# 19_SMB1358.net
KiCad netlist of a schematic drawn in Altium Designer
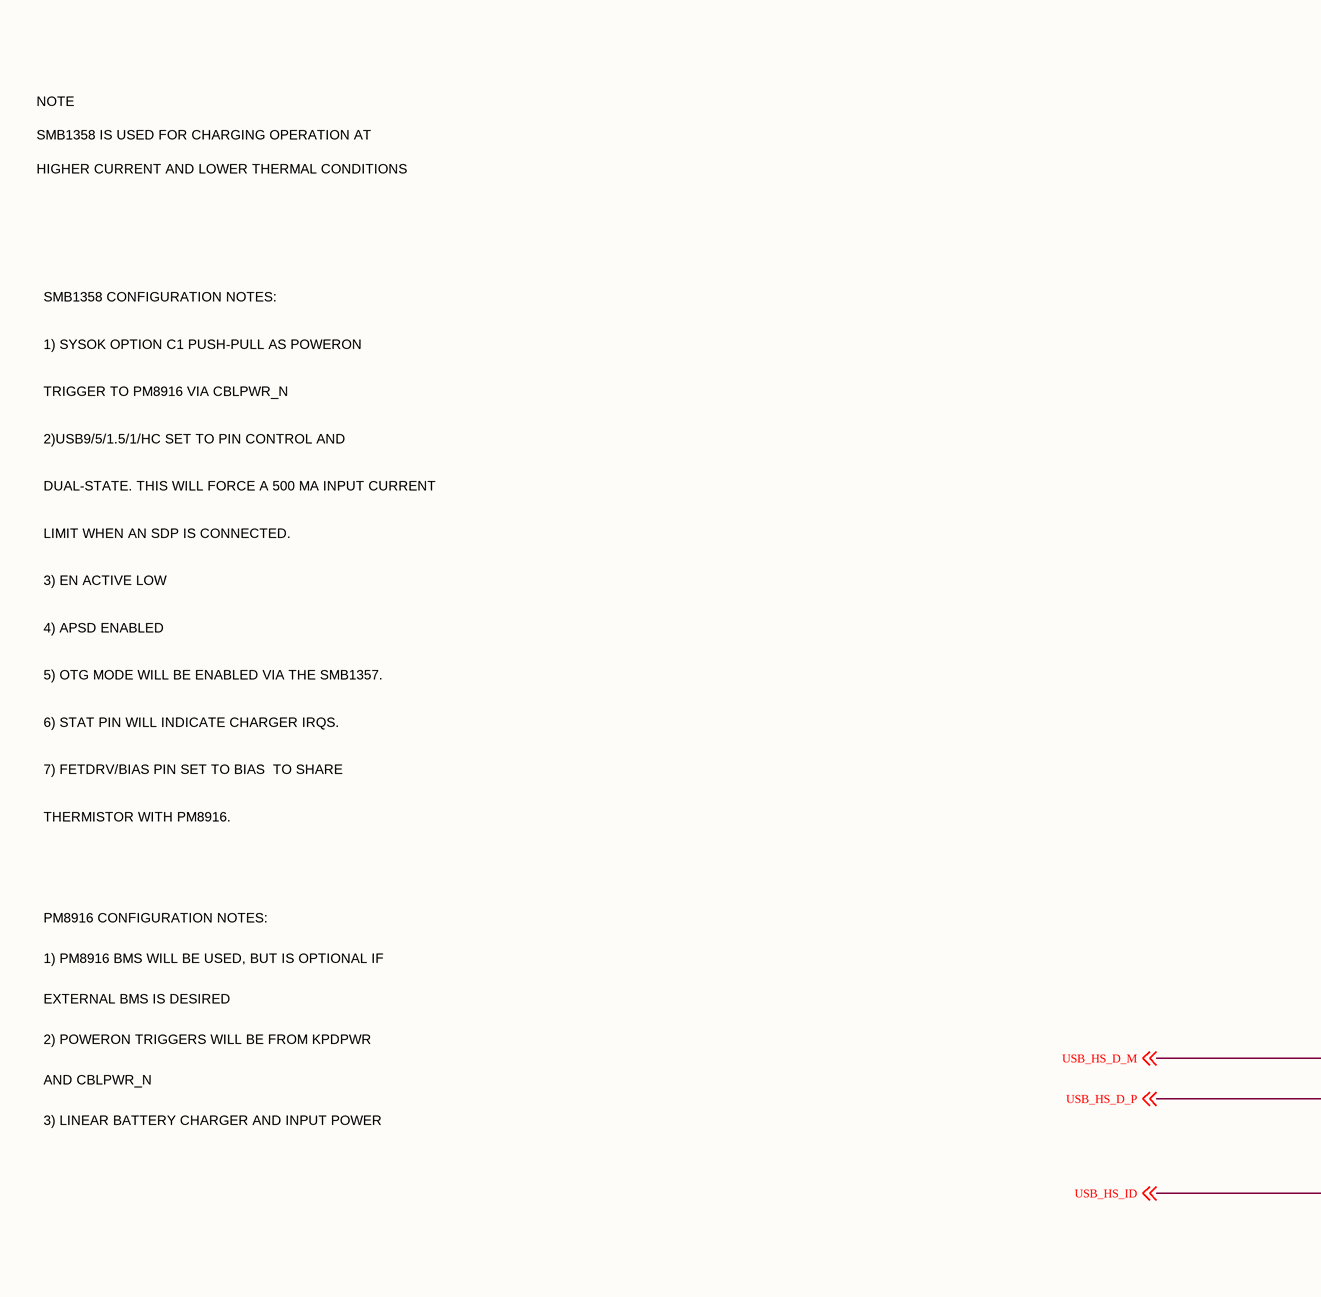
[diagram p0: 19 SMB1358.SchDoc, top left]
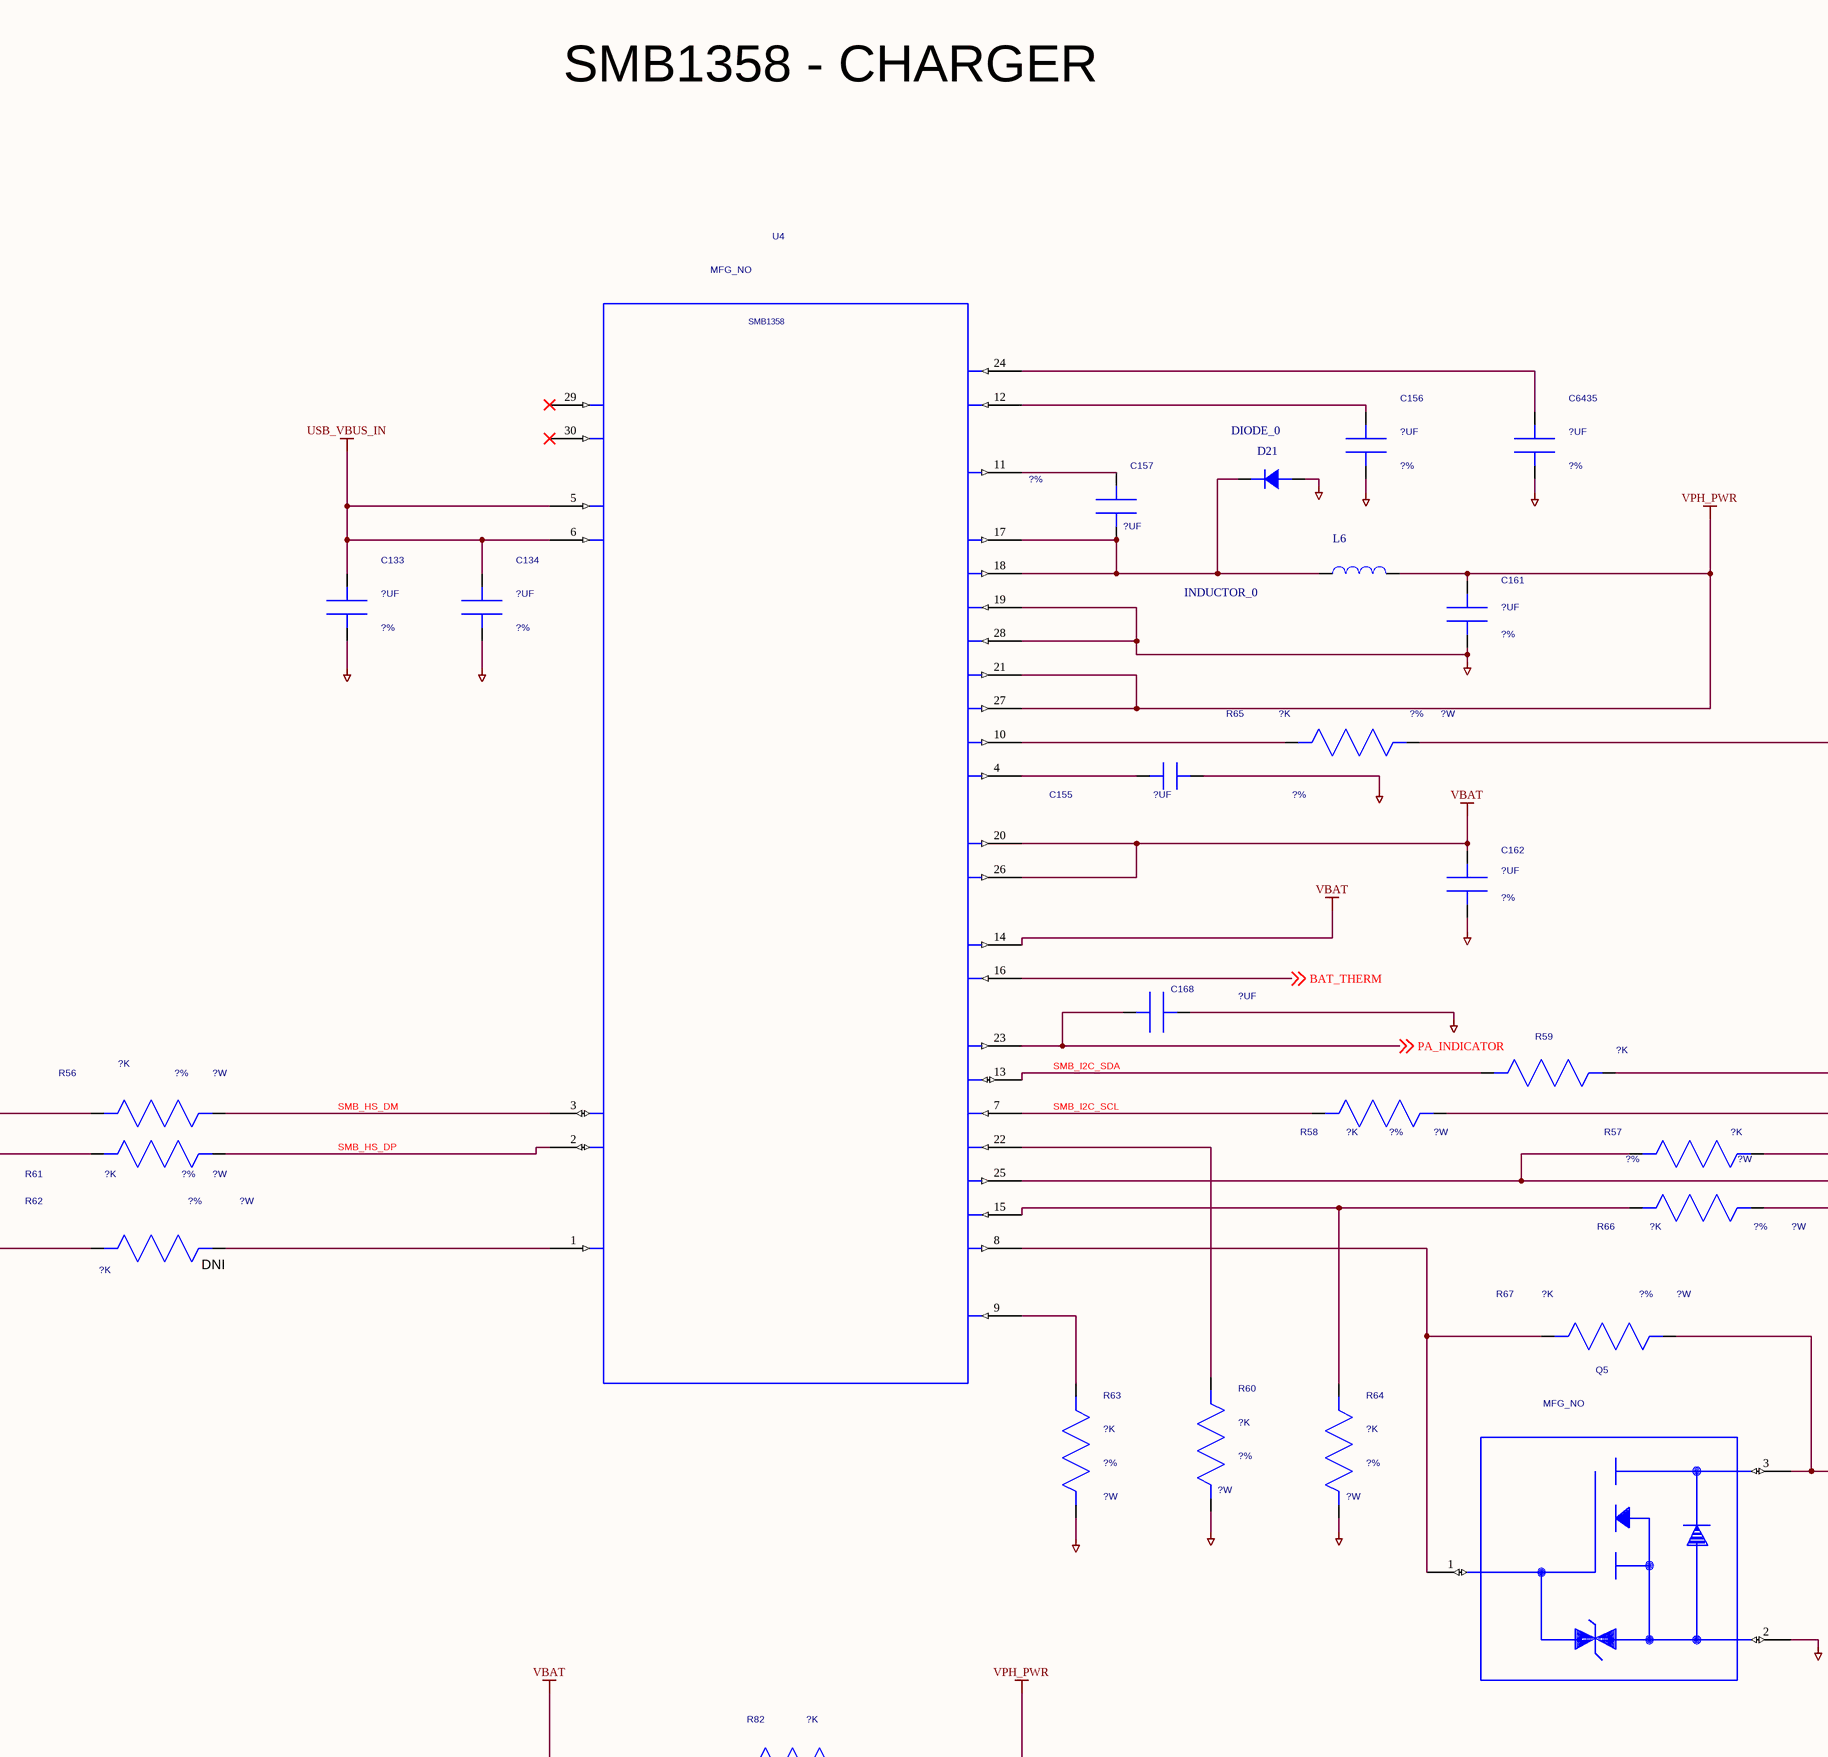
[diagram p1: 19 SMB1358.SchDoc, top middle]
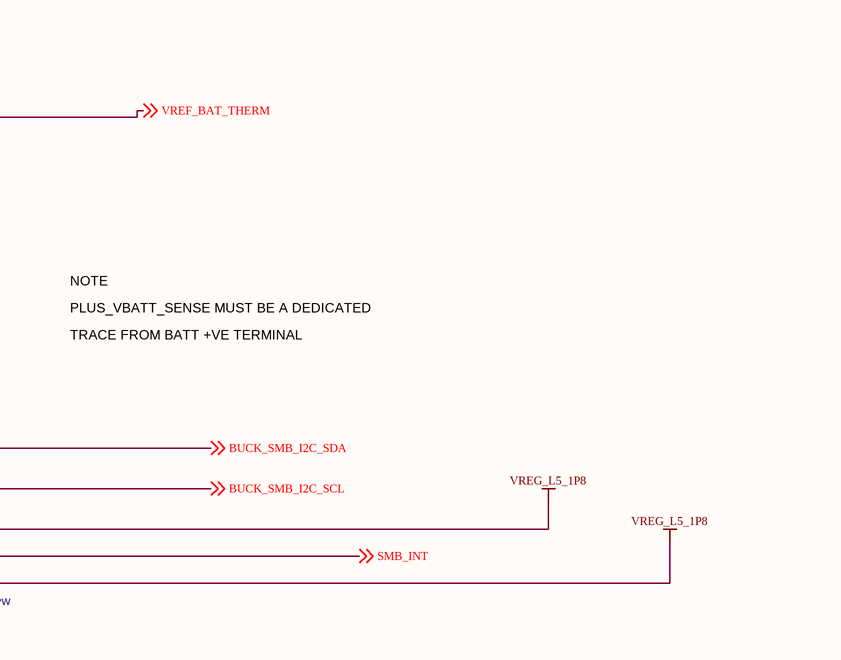
[diagram p2: 19 SMB1358.SchDoc, top right]
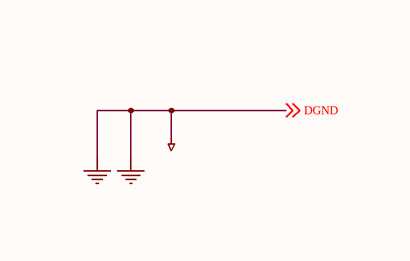
[diagram p3: 19 SMB1358.SchDoc, bottom left]
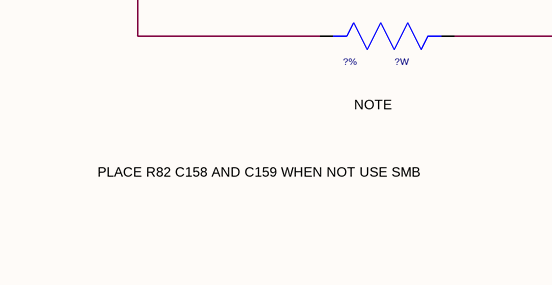
[diagram p4: 19 SMB1358.SchDoc, bottom middle]
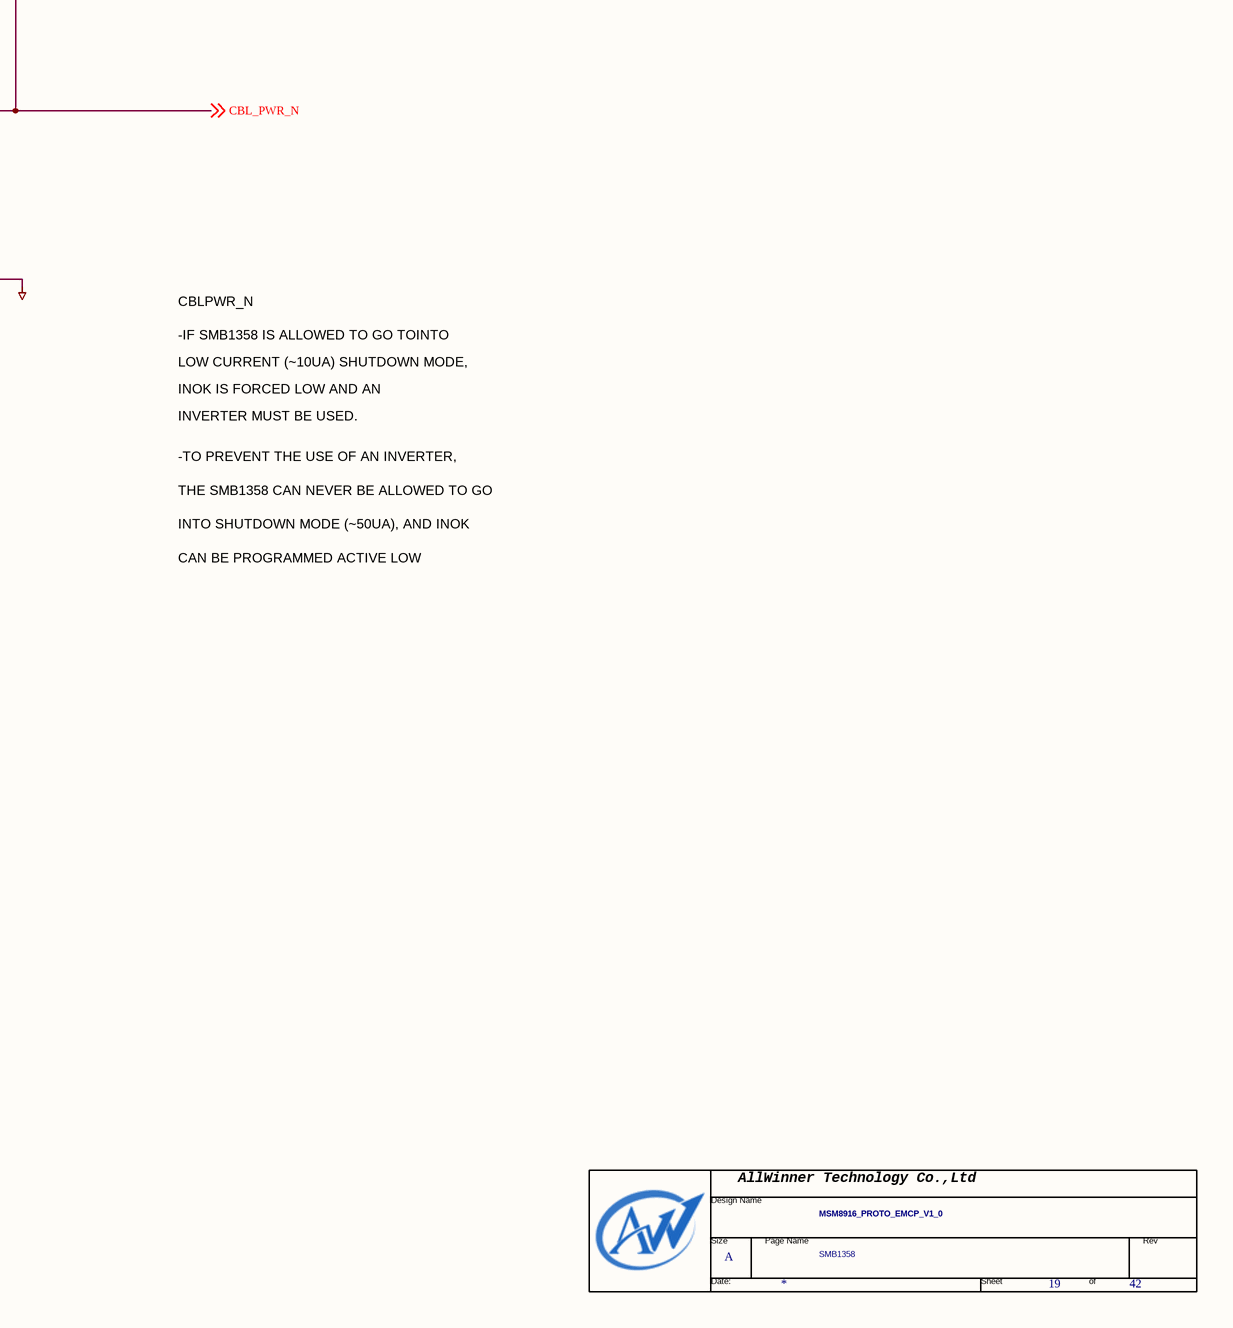
[diagram p5: 19 SMB1358.SchDoc, bottom right]

(export (version "E")
  (design (tool "Eeschema 10.0.6"))
  (components
    (comp (ref "*")
      (value "TitleBlock0-AW")
      (fields
        (field (name "PAGE COUNT") "42")
        (field (name "PAGE NUMBER") "19")
        (field (name "PAGE SIZE") "A")
        (field (name "TITLE") "MSM8916_PROTO_EMCP_V1_0")
        (field (name "DOC") "SMB1358")
      )
      (libsource (lib "*") (part "TitleBlock0-AW"))
    )
    (comp (ref "C133")
      (value "?UF")
      (fields (field (name "TOLERANCE") "?%") (field (name "PART_NUMBER") "MCN_NO"))
      (libsource (lib "MSM8916_DRAM_PMIC_REF_Library") (part "CAP"))
    )
    (comp (ref "C134")
      (value "?UF")
      (fields (field (name "TOLERANCE") "?%") (field (name "PART_NUMBER") "MCN_NO"))
      (libsource (lib "MSM8916_DRAM_PMIC_REF_Library") (part "CAP"))
    )
    (comp (ref "C155")
      (value "?UF")
      (fields (field (name "TOLERANCE") "?%") (field (name "PART_NUMBER") "MCN_NO"))
      (libsource (lib "MSM8916_DRAM_PMIC_REF_Library") (part "CAP#1"))
    )
    (comp (ref "C156")
      (value "?UF")
      (fields (field (name "TOLERANCE") "?%") (field (name "PART_NUMBER") "MCN_NO"))
      (libsource (lib "MSM8916_DRAM_PMIC_REF_Library") (part "CAP"))
    )
    (comp (ref "C157")
      (value "?UF")
      (fields (field (name "TOLERANCE") "?%") (field (name "PART_NUMBER") "MCN_NO"))
      (libsource (lib "MSM8916_DRAM_PMIC_REF_Library") (part "CAP"))
    )
    (comp (ref "C161")
      (value "?UF")
      (fields (field (name "TOLERANCE") "?%") (field (name "PART_NUMBER") "MCN_NO"))
      (libsource (lib "MSM8916_DRAM_PMIC_REF_Library") (part "CAP"))
    )
    (comp (ref "C162")
      (value "?UF")
      (fields (field (name "TOLERANCE") "?%") (field (name "PART_NUMBER") "MCN_NO"))
      (libsource (lib "MSM8916_DRAM_PMIC_REF_Library") (part "CAP"))
    )
    (comp (ref "C168")
      (value "?UF")
      (fields (field (name "TOLERANCE") "?%") (field (name "PART_NUMBER") "MCN_NO"))
      (libsource (lib "MSM8916_DRAM_PMIC_REF_Library") (part "CAP"))
    )
    (comp (ref "C6435")
      (value "?UF")
      (fields (field (name "TOLERANCE") "?%") (field (name "PART_NUMBER") "MCN_NO"))
      (libsource (lib "MSM8916_DRAM_PMIC_REF_Library") (part "CAP"))
    )
    (comp (ref "D21") (value "DIODE_0") (libsource (lib "MSM8916_DRAM_PMIC_REF_Library") (part "DIODE_0")))
    (comp (ref "L6")
      (value "INDUCTOR_0")
      (libsource (lib "MSM8916_DRAM_PMIC_REF_Library") (part "INDUCTOR_0"))
    )
    (comp (ref "Q5")
      (value "nfet_zener_bidir")
      (fields (field (name "PART_NUMBER") "MCN_NO") (field (name "PART_ID") "MFG_NO"))
      (libsource (lib "MSM8916_DRAM_PMIC_REF_Library") (part "NFET_ZENER_BIDIR"))
    )
    (comp (ref "R56")
      (value "?K")
      (fields
        (field (name "TOLERANCE") "?%")
        (field (name "POWER") "?W")
        (field (name "PART_NUMBER") "MCN_NO")
      )
      (libsource (lib "MSM8916_DRAM_PMIC_REF_Library") (part "RESISTOR_Dup3"))
    )
    (comp (ref "R57")
      (value "?K")
      (fields
        (field (name "TOLERANCE") "?%")
        (field (name "POWER") "?W")
        (field (name "PART_NUMBER") "MCN_NO")
      )
      (libsource (lib "MSM8916_DRAM_PMIC_REF_Library") (part "RESISTOR_Dup3"))
    )
    (comp (ref "R58")
      (value "?K")
      (fields
        (field (name "TOLERANCE") "?%")
        (field (name "POWER") "?W")
        (field (name "PART_NUMBER") "MCN_NO")
      )
      (libsource (lib "MSM8916_DRAM_PMIC_REF_Library") (part "RESISTOR_Dup3"))
    )
    (comp (ref "R59")
      (value "?K")
      (fields
        (field (name "TOLERANCE") "?%")
        (field (name "POWER") "?W")
        (field (name "PART_NUMBER") "MCN_NO")
      )
      (libsource (lib "MSM8916_DRAM_PMIC_REF_Library") (part "RESISTOR_Dup3"))
    )
    (comp (ref "R60")
      (value "?K")
      (fields
        (field (name "TOLERANCE") "?%")
        (field (name "POWER") "?W")
        (field (name "PART_NUMBER") "MCN_NO")
      )
      (libsource (lib "MSM8916_DRAM_PMIC_REF_Library") (part "RESISTOR#1"))
    )
    (comp (ref "R61")
      (value "?K")
      (fields
        (field (name "TOLERANCE") "?%")
        (field (name "POWER") "?W")
        (field (name "PART_NUMBER") "MCN_NO")
      )
      (libsource (lib "MSM8916_DRAM_PMIC_REF_Library") (part "RESISTOR_Dup3"))
    )
    (comp (ref "R62")
      (value "?K")
      (fields
        (field (name "TOLERANCE") "?%")
        (field (name "POWER") "?W")
        (field (name "PART_NUMBER") "MCN_NO")
      )
      (libsource (lib "MSM8916_DRAM_PMIC_REF_Library") (part "RESISTOR_Dup3"))
    )
    (comp (ref "R63")
      (value "?K")
      (fields
        (field (name "TOLERANCE") "?%")
        (field (name "POWER") "?W")
        (field (name "PART_NUMBER") "MCN_NO")
      )
      (libsource (lib "MSM8916_DRAM_PMIC_REF_Library") (part "RESISTOR#1"))
    )
    (comp (ref "R64")
      (value "?K")
      (fields
        (field (name "TOLERANCE") "?%")
        (field (name "POWER") "?W")
        (field (name "PART_NUMBER") "MCN_NO")
      )
      (libsource (lib "MSM8916_DRAM_PMIC_REF_Library") (part "RESISTOR#1"))
    )
    (comp (ref "R65")
      (value "?K")
      (fields
        (field (name "TOLERANCE") "?%")
        (field (name "POWER") "?W")
        (field (name "PART_NUMBER") "MCN_NO")
      )
      (libsource (lib "MSM8916_DRAM_PMIC_REF_Library") (part "RESISTOR_Dup3"))
    )
    (comp (ref "R66")
      (value "?K")
      (fields
        (field (name "TOLERANCE") "?%")
        (field (name "POWER") "?W")
        (field (name "PART_NUMBER") "MCN_NO")
      )
      (libsource (lib "MSM8916_DRAM_PMIC_REF_Library") (part "RESISTOR_Dup3"))
    )
    (comp (ref "R67")
      (value "?K")
      (fields
        (field (name "TOLERANCE") "?%")
        (field (name "POWER") "?W")
        (field (name "PART_NUMBER") "MCN_NO")
      )
      (libsource (lib "MSM8916_DRAM_PMIC_REF_Library") (part "RESISTOR_Dup3"))
    )
    (comp (ref "R82")
      (value "?K")
      (fields
        (field (name "TOLERANCE") "?%")
        (field (name "POWER") "?W")
        (field (name "PART_NUMBER") "MCN_NO")
      )
      (libsource (lib "MSM8916_DRAM_PMIC_REF_Library") (part "RESISTOR_Dup3"))
    )
    (comp (ref "U4")
      (value "asic_smb1358")
      (fields
        (field (name "PART_NUMBER") "MCN_NO")
        (field (name "PART_ID") "MFG_NO")
        (field (name "BLOCKID") "SMB1358")
      )
      (libsource (lib "MSM8916_DRAM_PMIC_REF_Library") (part "ASIC_SMB1358"))
    )
  )
  (nets
    (net (code "1") (name "/SMB_HS_DM") (class "Default")
      (node (ref "R56") (pin "2") (pinfunction "NEG_2") (pintype "bidirectional"))
      (node (ref "U4") (pin "3") (pinfunction "DM_3") (pintype "bidirectional"))
    )
    (net (code "2") (name "/SMB_HS_DP") (class "Default")
      (node (ref "R61") (pin "2") (pinfunction "NEG_2") (pintype "bidirectional"))
      (node (ref "U4") (pin "2") (pinfunction "DP_2") (pintype "bidirectional"))
    )
    (net (code "3") (name "/SMB_I2C_SCL") (class "Default")
      (node (ref "R58") (pin "1") (pinfunction "POS_1") (pintype "bidirectional"))
      (node (ref "U4") (pin "7") (pinfunction "SCL_7") (pintype "input"))
    )
    (net (code "4") (name "/SMB_I2C_SDA") (class "Default")
      (node (ref "R59") (pin "1") (pinfunction "POS_1") (pintype "bidirectional"))
      (node (ref "U4") (pin "13") (pinfunction "SDA_13") (pintype "bidirectional"))
    )
    (net (code "5") (name "BAT_THERM") (class "Default")
      (node (ref "U4") (pin "16") (pinfunction "THERM_16") (pintype "input"))
    )
    (net (code "6") (name "BUCK_SMB_I2C_SCL") (class "Default")
      (node (ref "R58") (pin "2") (pinfunction "NEG_2") (pintype "bidirectional"))
    )
    (net (code "7") (name "BUCK_SMB_I2C_SDA") (class "Default")
      (node (ref "R59") (pin "2") (pinfunction "NEG_2") (pintype "bidirectional"))
    )
    (net (code "8") (name "CBL_PWR_N") (class "Default")
      (node (ref "Q5") (pin "3") (pinfunction "D_3") (pintype "bidirectional"))
      (node (ref "R67") (pin "2") (pinfunction "NEG_2") (pintype "bidirectional"))
    )
    (net (code "9") (name "DGND") (class "Default")
      (node (ref "C133") (pin "2") (pinfunction "NEG_2") (pintype "bidirectional"))
      (node (ref "C134") (pin "2") (pinfunction "NEG_2") (pintype "bidirectional"))
      (node (ref "C155") (pin "1") (pinfunction "POS_1") (pintype "bidirectional"))
      (node (ref "C156") (pin "2") (pinfunction "NEG_2") (pintype "bidirectional"))
      (node (ref "C161") (pin "2") (pinfunction "NEG_2") (pintype "bidirectional"))
      (node (ref "C162") (pin "2") (pinfunction "NEG_2") (pintype "bidirectional"))
      (node (ref "C168") (pin "2") (pinfunction "NEG_2") (pintype "bidirectional"))
      (node (ref "C6435") (pin "2") (pinfunction "NEG_2") (pintype "bidirectional"))
      (node (ref "D21") (pin "2") (pinfunction "K_2") (pintype "passive"))
      (node (ref "Q5") (pin "2") (pinfunction "S_2") (pintype "bidirectional"))
      (node (ref "R60") (pin "2") (pinfunction "NEG_2") (pintype "bidirectional"))
      (node (ref "R63") (pin "2") (pinfunction "NEG_2") (pintype "bidirectional"))
      (node (ref "R64") (pin "2") (pinfunction "NEG_2") (pintype "bidirectional"))
      (node (ref "U4") (pin "19") (pinfunction "GND_19") (pintype "input"))
      (node (ref "U4") (pin "28") (pinfunction "PGND_28") (pintype "input"))
    )
    (net (code "10") (name "Net-(C155-NEG)") (class "Default")
      (node (ref "C155") (pin "2") (pinfunction "NEG_2") (pintype "bidirectional"))
      (node (ref "U4") (pin "4") (pinfunction "SYSON_4") (pintype "output"))
    )
    (net (code "11") (name "Net-(C156-POS)") (class "Default")
      (node (ref "C156") (pin "1") (pinfunction "POS_1") (pintype "bidirectional"))
      (node (ref "U4") (pin "12") (pinfunction "MIDUSBIN_12") (pintype "input"))
    )
    (net (code "12") (name "Net-(C157-NEG)") (class "Default")
      (node (ref "C157") (pin "2") (pinfunction "NEG_2") (pintype "bidirectional"))
      (node (ref "D21") (pin "1") (pinfunction "A_1") (pintype "passive"))
      (node (ref "L6") (pin "1") (pinfunction "1_1") (pintype "passive"))
      (node (ref "U4") (pin "17") (pinfunction "SW1_17") (pintype "output"))
      (node (ref "U4") (pin "18") (pinfunction "SW2_18") (pintype "output"))
    )
    (net (code "13") (name "Net-(C157-POS)") (class "Default")
      (node (ref "C157") (pin "1") (pinfunction "POS_1") (pintype "bidirectional"))
      (node (ref "U4") (pin "11") (pinfunction "BOOT_11") (pintype "output"))
    )
    (net (code "14") (name "Net-(C6435-POS)") (class "Default")
      (node (ref "C6435") (pin "1") (pinfunction "POS_1") (pintype "bidirectional"))
      (node (ref "U4") (pin "24") (pinfunction "MIDDCIN_24") (pintype "input"))
    )
    (net (code "15") (name "Net-(Q5-G)") (class "Default")
      (node (ref "Q5") (pin "1") (pinfunction "G_1") (pintype "bidirectional"))
      (node (ref "R67") (pin "1") (pinfunction "POS_1") (pintype "bidirectional"))
      (node (ref "U4") (pin "8") (pinfunction "SYSOK_8") (pintype "output"))
    )
    (net (code "16") (name "Net-(R60-POS)") (class "Default")
      (node (ref "R60") (pin "1") (pinfunction "POS_1") (pintype "bidirectional"))
      (node (ref "U4") (pin "22") (pinfunction "EN_22") (pintype "input"))
    )
    (net (code "17") (name "Net-(R62-NEG)") (class "Default")
      (node (ref "R62") (pin "2") (pinfunction "NEG_2") (pintype "bidirectional"))
      (node (ref "U4") (pin "1") (pinfunction "OTG_1") (pintype "input"))
    )
    (net (code "18") (name "Net-(R63-POS)") (class "Default")
      (node (ref "R63") (pin "1") (pinfunction "POS_1") (pintype "bidirectional"))
      (node (ref "U4") (pin "9") (pinfunction "USB5_9") (pintype "input"))
    )
    (net (code "19") (name "Net-(R64-POS)") (class "Default")
      (node (ref "R64") (pin "1") (pinfunction "POS_1") (pintype "bidirectional"))
      (node (ref "R66") (pin "1") (pinfunction "POS_1") (pintype "bidirectional"))
      (node (ref "U4") (pin "15") (pinfunction "SUSP_15") (pintype "input"))
    )
    (net (code "20") (name "Net-(R65-POS)") (class "Default")
      (node (ref "R65") (pin "1") (pinfunction "POS_1") (pintype "bidirectional"))
      (node (ref "U4") (pin "10") (pinfunction "BIAS_10") (pintype "output"))
    )
    (net (code "21") (name "PA_INDICATOR") (class "Default")
      (node (ref "C168") (pin "1") (pinfunction "POS_1") (pintype "bidirectional"))
      (node (ref "U4") (pin "23") (pinfunction "VCHG_23") (pintype "output"))
    )
    (net (code "22") (name "SMB_INT") (class "Default")
      (node (ref "R57") (pin "1") (pinfunction "POS_1") (pintype "bidirectional"))
      (node (ref "U4") (pin "25") (pinfunction "STAT_25") (pintype "output"))
    )
    (net (code "23") (name "USB_HS_D_M") (class "Default")
      (node (ref "R56") (pin "1") (pinfunction "POS_1") (pintype "bidirectional"))
    )
    (net (code "24") (name "USB_HS_D_P") (class "Default")
      (node (ref "R61") (pin "1") (pinfunction "POS_1") (pintype "bidirectional"))
    )
    (net (code "25") (name "USB_HS_ID") (class "Default")
      (node (ref "R62") (pin "1") (pinfunction "POS_1") (pintype "bidirectional"))
    )
    (net (code "26") (name "USB_VBUS_IN") (class "Default")
      (node (ref "C133") (pin "1") (pinfunction "POS_1") (pintype "bidirectional"))
      (node (ref "C134") (pin "1") (pinfunction "POS_1") (pintype "bidirectional"))
      (node (ref "U4") (pin "5") (pinfunction "USBIN1_5") (pintype "input"))
      (node (ref "U4") (pin "6") (pinfunction "USBIN2_6") (pintype "input"))
    )
    (net (code "27") (name "VBAT") (class "Default")
      (node (ref "C162") (pin "1") (pinfunction "POS_1") (pintype "bidirectional"))
      (node (ref "R82") (pin "1") (pinfunction "POS_1") (pintype "bidirectional"))
      (node (ref "U4") (pin "14") (pinfunction "VBATT_14") (pintype "output"))
      (node (ref "U4") (pin "20") (pinfunction "CHGOUT1_20") (pintype "output"))
      (node (ref "U4") (pin "26") (pinfunction "CHGOUT2_26") (pintype "output"))
    )
    (net (code "28") (name "VPH_PWR") (class "Default")
      (node (ref "C161") (pin "1") (pinfunction "POS_1") (pintype "bidirectional"))
      (node (ref "L6") (pin "2") (pinfunction "2_2") (pintype "passive"))
      (node (ref "R82") (pin "2") (pinfunction "NEG_2") (pintype "bidirectional"))
      (node (ref "U4") (pin "21") (pinfunction "VSYS1_21") (pintype "output"))
      (node (ref "U4") (pin "27") (pinfunction "VSYS2_27") (pintype "output"))
    )
    (net (code "29") (name "VREF_BAT_THERM") (class "Default")
      (node (ref "R65") (pin "2") (pinfunction "NEG_2") (pintype "bidirectional"))
    )
    (net (code "30") (name "VREG_L5_1P8") (class "Default")
      (node (ref "R57") (pin "2") (pinfunction "NEG_2") (pintype "bidirectional"))
      (node (ref "R66") (pin "2") (pinfunction "NEG_2") (pintype "bidirectional"))
    )
    (net (code "31") (name "unconnected-(U4-DCIN1-Pad29)") (class "Default")
      (node (ref "U4") (pin "29") (pinfunction "DCIN1_29") (pintype "input+no_connect"))
    )
    (net (code "32") (name "unconnected-(U4-DCIN2-Pad30)") (class "Default")
      (node (ref "U4") (pin "30") (pinfunction "DCIN2_30") (pintype "input+no_connect"))
    )
  )
)
